# 433MHz_LNA.net
KiCad netlist of a schematic drawn in Altium Designer
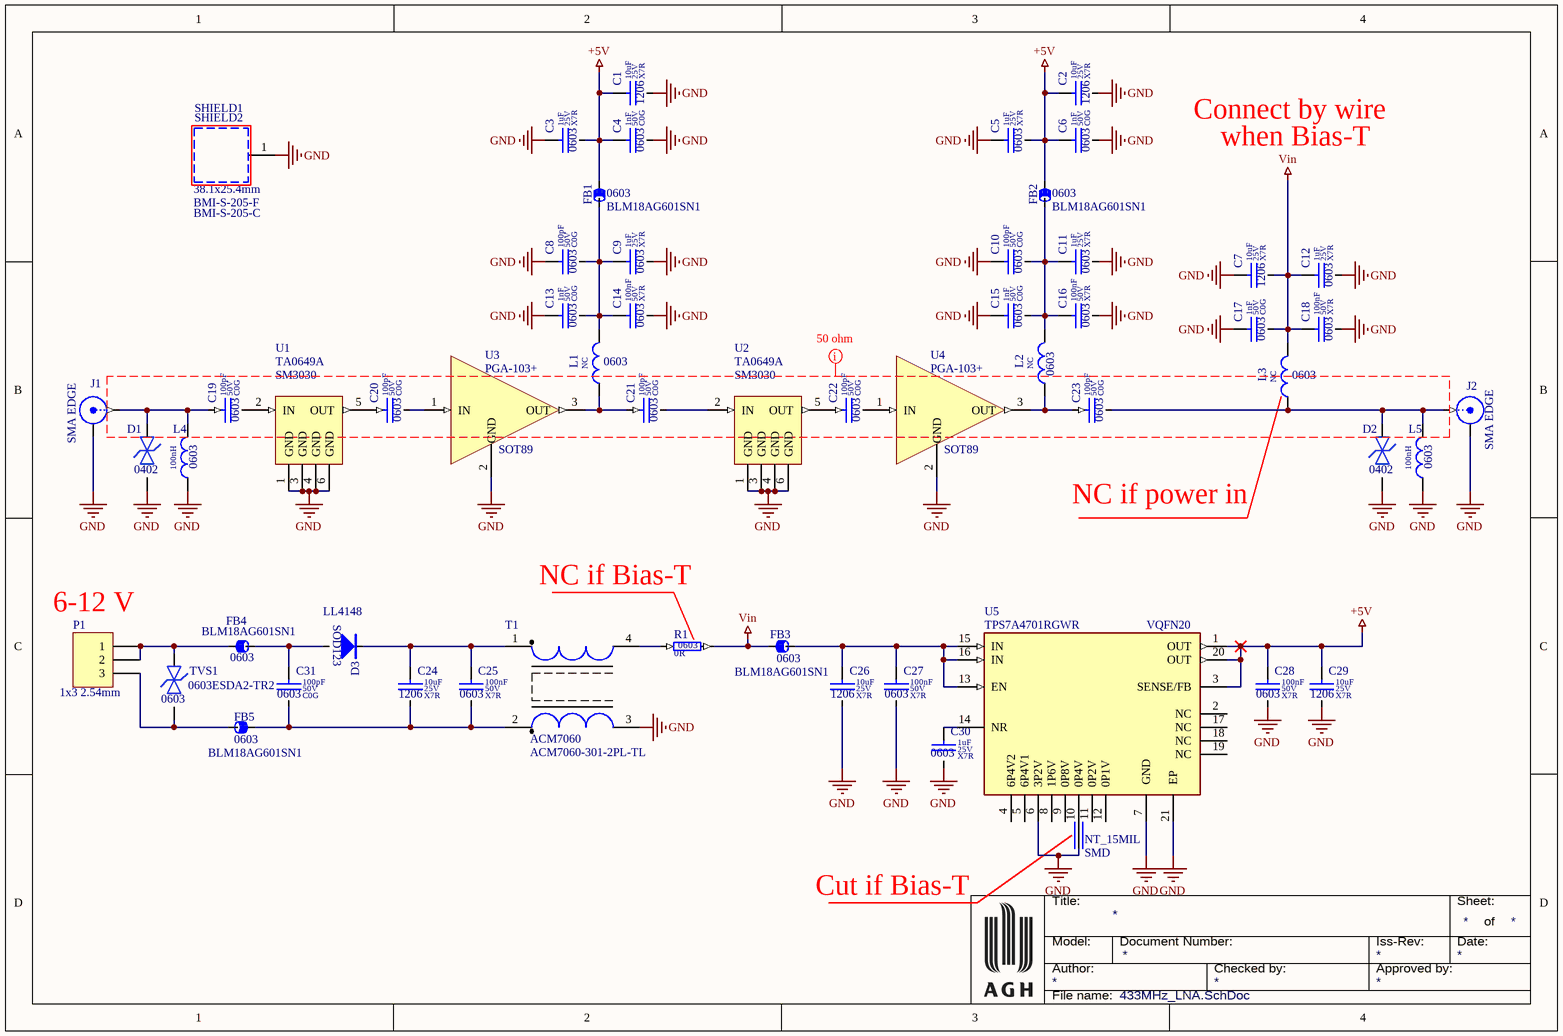
[diagram p0: 433MHz_LNA.SchDoc]

(export (version "E")
  (design (tool "Eeschema 10.0.6"))
  (components
    (comp (ref "C1")
      (value "10uF")
      (footprint "C_1206_3216")
      (description "Capacitor")
      (fields
        (field (name "DIELECTRIC") "X7R")
        (field (name "VOLTAGE") "25V")
        (field (name "SCH_FOOTPRINT") "1206")
        (field (name "PART NUMBER") "C_10uF_25V_X7R_1206_10")
        (field (name "MANUFACTURER") "Samsung Electro-Mechanics")
      )
      (libsource (lib "Library") (part "C"))
    )
    (comp (ref "C2")
      (value "10uF")
      (footprint "C_1206_3216")
      (description "Capacitor")
      (fields
        (field (name "DIELECTRIC") "X7R")
        (field (name "VOLTAGE") "25V")
        (field (name "SCH_FOOTPRINT") "1206")
        (field (name "PART NUMBER") "C_10uF_25V_X7R_1206_10")
        (field (name "MANUFACTURER") "Samsung Electro-Mechanics")
      )
      (libsource (lib "Library") (part "C"))
    )
    (comp (ref "C3")
      (value "1uF")
      (footprint "C_0603_1608")
      (description "Capacitor")
      (fields
        (field (name "DIELECTRIC") "X7R")
        (field (name "VOLTAGE") "25V")
        (field (name "SCH_FOOTPRINT") "0603")
        (field (name "PART NUMBER") "C_1uF_25V_X7R_0603_10")
        (field (name "MANUFACTURER") "Samsung")
      )
      (libsource (lib "Library") (part "C"))
    )
    (comp (ref "C4")
      (value "1nF")
      (footprint "C_0603_1608")
      (description "Capacitor")
      (fields
        (field (name "DIELECTRIC") "C0G")
        (field (name "VOLTAGE") "50V")
        (field (name "SCH_FOOTPRINT") "0603")
        (field (name "PART NUMBER") "C_1nF_50V_C0G_0603_5")
        (field (name "MANUFACTURER") "Samsung")
      )
      (libsource (lib "Library") (part "C"))
    )
    (comp (ref "C5")
      (value "1uF")
      (footprint "C_0603_1608")
      (description "Capacitor")
      (fields
        (field (name "DIELECTRIC") "X7R")
        (field (name "VOLTAGE") "25V")
        (field (name "SCH_FOOTPRINT") "0603")
        (field (name "PART NUMBER") "C_1uF_25V_X7R_0603_10")
        (field (name "MANUFACTURER") "Samsung")
      )
      (libsource (lib "Library") (part "C"))
    )
    (comp (ref "C6")
      (value "1nF")
      (footprint "C_0603_1608")
      (description "Capacitor")
      (fields
        (field (name "DIELECTRIC") "C0G")
        (field (name "VOLTAGE") "50V")
        (field (name "SCH_FOOTPRINT") "0603")
        (field (name "PART NUMBER") "C_1nF_50V_C0G_0603_5")
        (field (name "MANUFACTURER") "Samsung")
      )
      (libsource (lib "Library") (part "C"))
    )
    (comp (ref "C7")
      (value "10uF")
      (footprint "C_1206_3216")
      (description "Capacitor")
      (fields
        (field (name "DIELECTRIC") "X7R")
        (field (name "VOLTAGE") "25V")
        (field (name "SCH_FOOTPRINT") "1206")
        (field (name "PART NUMBER") "C_10uF_25V_X7R_1206_10")
        (field (name "MANUFACTURER") "Samsung Electro-Mechanics")
      )
      (libsource (lib "Library") (part "C"))
    )
    (comp (ref "C8")
      (value "100pF")
      (footprint "C_0603_1608")
      (description "Capacitor")
      (fields
        (field (name "DIELECTRIC") "C0G")
        (field (name "VOLTAGE") "50V")
        (field (name "SCH_FOOTPRINT") "0603")
        (field (name "PART NUMBER") "C_100pF_50V_C0G_0603_5")
        (field (name "MANUFACTURER") "AVX")
      )
      (libsource (lib "Library") (part "C"))
    )
    (comp (ref "C9")
      (value "1uF")
      (footprint "C_0603_1608")
      (description "Capacitor")
      (fields
        (field (name "DIELECTRIC") "X7R")
        (field (name "VOLTAGE") "25V")
        (field (name "SCH_FOOTPRINT") "0603")
        (field (name "PART NUMBER") "C_1uF_25V_X7R_0603_10")
        (field (name "MANUFACTURER") "Samsung")
      )
      (libsource (lib "Library") (part "C"))
    )
    (comp (ref "C10")
      (value "100pF")
      (footprint "C_0603_1608")
      (description "Capacitor")
      (fields
        (field (name "DIELECTRIC") "C0G")
        (field (name "VOLTAGE") "50V")
        (field (name "SCH_FOOTPRINT") "0603")
        (field (name "PART NUMBER") "C_100pF_50V_C0G_0603_5")
        (field (name "MANUFACTURER") "AVX")
      )
      (libsource (lib "Library") (part "C"))
    )
    (comp (ref "C11")
      (value "1uF")
      (footprint "C_0603_1608")
      (description "Capacitor")
      (fields
        (field (name "DIELECTRIC") "X7R")
        (field (name "VOLTAGE") "25V")
        (field (name "SCH_FOOTPRINT") "0603")
        (field (name "PART NUMBER") "C_1uF_25V_X7R_0603_10")
        (field (name "MANUFACTURER") "Samsung")
      )
      (libsource (lib "Library") (part "C"))
    )
    (comp (ref "C12")
      (value "1uF")
      (footprint "C_0603_1608")
      (description "Capacitor")
      (fields
        (field (name "DIELECTRIC") "X7R")
        (field (name "VOLTAGE") "25V")
        (field (name "SCH_FOOTPRINT") "0603")
        (field (name "PART NUMBER") "C_1uF_25V_X7R_0603_10")
        (field (name "MANUFACTURER") "Samsung")
      )
      (libsource (lib "Library") (part "C"))
    )
    (comp (ref "C13")
      (value "1nF")
      (footprint "C_0603_1608")
      (description "Capacitor")
      (fields
        (field (name "DIELECTRIC") "C0G")
        (field (name "VOLTAGE") "50V")
        (field (name "SCH_FOOTPRINT") "0603")
        (field (name "PART NUMBER") "C_1nF_50V_C0G_0603_5")
        (field (name "MANUFACTURER") "Samsung")
      )
      (libsource (lib "Library") (part "C"))
    )
    (comp (ref "C14")
      (value "100nF")
      (footprint "C_0603_1608")
      (description "Capacitor")
      (fields
        (field (name "DIELECTRIC") "X7R")
        (field (name "VOLTAGE") "50V")
        (field (name "SCH_FOOTPRINT") "0603")
        (field (name "PART NUMBER") "C_100nF_50V_X7R_0603_5")
        (field (name "MANUFACTURER") "Samsung")
      )
      (libsource (lib "Library") (part "C"))
    )
    (comp (ref "C15")
      (value "1nF")
      (footprint "C_0603_1608")
      (description "Capacitor")
      (fields
        (field (name "DIELECTRIC") "C0G")
        (field (name "VOLTAGE") "50V")
        (field (name "SCH_FOOTPRINT") "0603")
        (field (name "PART NUMBER") "C_1nF_50V_C0G_0603_5")
        (field (name "MANUFACTURER") "Samsung")
      )
      (libsource (lib "Library") (part "C"))
    )
    (comp (ref "C16")
      (value "100nF")
      (footprint "C_0603_1608")
      (description "Capacitor")
      (fields
        (field (name "DIELECTRIC") "X7R")
        (field (name "VOLTAGE") "50V")
        (field (name "SCH_FOOTPRINT") "0603")
        (field (name "PART NUMBER") "C_100nF_50V_X7R_0603_5")
        (field (name "MANUFACTURER") "Samsung")
      )
      (libsource (lib "Library") (part "C"))
    )
    (comp (ref "C17")
      (value "1nF")
      (footprint "C_0603_1608")
      (description "Capacitor")
      (fields
        (field (name "DIELECTRIC") "C0G")
        (field (name "VOLTAGE") "50V")
        (field (name "SCH_FOOTPRINT") "0603")
        (field (name "PART NUMBER") "C_1nF_50V_C0G_0603_5")
        (field (name "MANUFACTURER") "Samsung")
      )
      (libsource (lib "Library") (part "C"))
    )
    (comp (ref "C18")
      (value "100nF")
      (footprint "C_0603_1608")
      (description "Capacitor")
      (fields
        (field (name "DIELECTRIC") "X7R")
        (field (name "VOLTAGE") "50V")
        (field (name "SCH_FOOTPRINT") "0603")
        (field (name "PART NUMBER") "C_100nF_50V_X7R_0603_5")
        (field (name "MANUFACTURER") "Samsung")
      )
      (libsource (lib "Library") (part "C"))
    )
    (comp (ref "C19")
      (value "100pF")
      (footprint "C_0603_1608")
      (description "Capacitor")
      (fields
        (field (name "DIELECTRIC") "C0G")
        (field (name "VOLTAGE") "50V")
        (field (name "SCH_FOOTPRINT") "0603")
        (field (name "PART NUMBER") "C_100pF_50V_C0G_0603_5")
        (field (name "MANUFACTURER") "AVX")
      )
      (libsource (lib "") (part "C_1"))
    )
    (comp (ref "C20")
      (value "100pF")
      (footprint "C_0603_1608")
      (description "Capacitor")
      (fields
        (field (name "DIELECTRIC") "C0G")
        (field (name "VOLTAGE") "50V")
        (field (name "SCH_FOOTPRINT") "0603")
        (field (name "PART NUMBER") "C_100pF_50V_C0G_0603_5")
        (field (name "MANUFACTURER") "AVX")
      )
      (libsource (lib "") (part "C_1"))
    )
    (comp (ref "C21")
      (value "100pF")
      (footprint "C_0603_1608")
      (description "Capacitor")
      (fields
        (field (name "DIELECTRIC") "C0G")
        (field (name "VOLTAGE") "50V")
        (field (name "SCH_FOOTPRINT") "0603")
        (field (name "PART NUMBER") "C_100pF_50V_C0G_0603_5")
        (field (name "MANUFACTURER") "AVX")
      )
      (libsource (lib "") (part "C_1"))
    )
    (comp (ref "C22")
      (value "100pF")
      (footprint "C_0603_1608")
      (description "Capacitor")
      (fields
        (field (name "DIELECTRIC") "C0G")
        (field (name "VOLTAGE") "50V")
        (field (name "SCH_FOOTPRINT") "0603")
        (field (name "PART NUMBER") "C_100pF_50V_C0G_0603_5")
        (field (name "MANUFACTURER") "AVX")
      )
      (libsource (lib "") (part "C_1"))
    )
    (comp (ref "C23")
      (value "100pF")
      (footprint "C_0603_1608")
      (description "Capacitor")
      (fields
        (field (name "DIELECTRIC") "C0G")
        (field (name "VOLTAGE") "50V")
        (field (name "SCH_FOOTPRINT") "0603")
        (field (name "PART NUMBER") "C_100pF_50V_C0G_0603_5")
        (field (name "MANUFACTURER") "AVX")
      )
      (libsource (lib "") (part "C_1"))
    )
    (comp (ref "C24")
      (value "10uF")
      (footprint "C_1206_3216")
      (description "Capacitor")
      (fields
        (field (name "DIELECTRIC") "X7R")
        (field (name "VOLTAGE") "25V")
        (field (name "SCH_FOOTPRINT") "1206")
        (field (name "PART NUMBER") "C_10uF_25V_X7R_1206_10")
        (field (name "MANUFACTURER") "Samsung Electro-Mechanics")
      )
      (libsource (lib "Library") (part "C"))
    )
    (comp (ref "C25")
      (value "100nF")
      (footprint "C_0603_1608")
      (description "Capacitor")
      (fields
        (field (name "DIELECTRIC") "X7R")
        (field (name "VOLTAGE") "50V")
        (field (name "SCH_FOOTPRINT") "0603")
        (field (name "PART NUMBER") "C_100nF_50V_X7R_0603_5")
        (field (name "MANUFACTURER") "Samsung")
      )
      (libsource (lib "Library") (part "C"))
    )
    (comp (ref "C26")
      (value "10uF")
      (footprint "C_1206_3216")
      (description "Capacitor")
      (fields
        (field (name "DIELECTRIC") "X7R")
        (field (name "VOLTAGE") "25V")
        (field (name "SCH_FOOTPRINT") "1206")
        (field (name "PART NUMBER") "C_10uF_25V_X7R_1206_10")
        (field (name "MANUFACTURER") "Samsung Electro-Mechanics")
      )
      (libsource (lib "Library") (part "C"))
    )
    (comp (ref "C27")
      (value "100nF")
      (footprint "C_0603_1608")
      (description "Capacitor")
      (fields
        (field (name "DIELECTRIC") "X7R")
        (field (name "VOLTAGE") "50V")
        (field (name "SCH_FOOTPRINT") "0603")
        (field (name "PART NUMBER") "C_100nF_50V_X7R_0603_5")
        (field (name "MANUFACTURER") "Samsung")
      )
      (libsource (lib "Library") (part "C"))
    )
    (comp (ref "C28")
      (value "100nF")
      (footprint "C_0603_1608")
      (description "Capacitor")
      (fields
        (field (name "DIELECTRIC") "X7R")
        (field (name "VOLTAGE") "50V")
        (field (name "SCH_FOOTPRINT") "0603")
        (field (name "PART NUMBER") "C_100nF_50V_X7R_0603_5")
        (field (name "MANUFACTURER") "Samsung")
      )
      (libsource (lib "Library") (part "C"))
    )
    (comp (ref "C29")
      (value "10uF")
      (footprint "C_1206_3216")
      (description "Capacitor")
      (fields
        (field (name "DIELECTRIC") "X7R")
        (field (name "VOLTAGE") "25V")
        (field (name "SCH_FOOTPRINT") "1206")
        (field (name "PART NUMBER") "C_10uF_25V_X7R_1206_10")
        (field (name "MANUFACTURER") "Samsung Electro-Mechanics")
      )
      (libsource (lib "Library") (part "C"))
    )
    (comp (ref "C30")
      (value "1uF")
      (footprint "C_0603_1608")
      (description "Capacitor")
      (fields
        (field (name "DIELECTRIC") "X7R")
        (field (name "VOLTAGE") "25V")
        (field (name "SCH_FOOTPRINT") "0603")
        (field (name "PART NUMBER") "C_1uF_25V_X7R_0603_10")
        (field (name "MANUFACTURER") "Samsung")
      )
      (libsource (lib "Library") (part "C"))
    )
    (comp (ref "C31")
      (value "100pF")
      (footprint "C_0603_1608")
      (description "Capacitor")
      (fields
        (field (name "DIELECTRIC") "C0G")
        (field (name "VOLTAGE") "50V")
        (field (name "SCH_FOOTPRINT") "0603")
        (field (name "PART NUMBER") "C_100pF_50V_C0G_0603_5")
        (field (name "MANUFACTURER") "AVX")
      )
      (libsource (lib "Library") (part "C"))
    )
    (comp (ref "D1")
      (value "ESD Suppressors / TVS Diodes")
      (footprint "D_BI_0402_1005")
      (fields
        (field (name "SCH_FOOTPRINT") "0402")
        (field (name "PART NUMBER") "TVS_PS04LTVA1")
        (field (name "VOLTAGE") "12V")
        (field (name "MANUFACTURER") "Bussmann")
      )
      (libsource (lib "Library") (part "TVS_BI"))
    )
    (comp (ref "D2")
      (value "ESD Suppressors / TVS Diodes")
      (footprint "D_BI_0402_1005")
      (fields
        (field (name "SCH_FOOTPRINT") "0402")
        (field (name "PART NUMBER") "TVS_PS04LTVA1")
        (field (name "VOLTAGE") "12V")
        (field (name "MANUFACTURER") "Bussmann")
      )
      (libsource (lib "Library") (part "TVS_BI"))
    )
    (comp (ref "D3")
      (value "LL4148")
      (footprint "SOD123")
      (fields
        (field (name "PART NUMBER") "D_1N4148W_0A15_75V_SOD123")
        (field (name "VOLTAGE") "75V")
        (field (name "MANUFACTURER") "Fairchild Semiconductor")
      )
      (libsource (lib "Library") (part "D"))
    )
    (comp (ref "FB1")
      (value "BLM18AG601SN1")
      (footprint "FB_0603_1608")
      (description "Ferrite Bead")
      (fields
        (field (name "PART NUMBER") "FB_BLM18AG601SN1")
        (field (name "SCH_FOOTPRINT") "0603")
        (field (name "MANUFACTURER") "Murata")
      )
      (libsource (lib "Library") (part "FB"))
    )
    (comp (ref "FB2")
      (value "BLM18AG601SN1")
      (footprint "FB_0603_1608")
      (description "Ferrite Bead")
      (fields
        (field (name "PART NUMBER") "FB_BLM18AG601SN1")
        (field (name "SCH_FOOTPRINT") "0603")
        (field (name "MANUFACTURER") "Murata")
      )
      (libsource (lib "Library") (part "FB"))
    )
    (comp (ref "FB3")
      (value "BLM18AG601SN1")
      (footprint "FB_0603_1608")
      (description "Ferrite Bead")
      (fields
        (field (name "PART NUMBER") "FB_BLM18AG601SN1")
        (field (name "SCH_FOOTPRINT") "0603")
        (field (name "MANUFACTURER") "Murata")
      )
      (libsource (lib "") (part "FB_2"))
    )
    (comp (ref "FB4")
      (value "BLM18AG601SN1")
      (footprint "FB_0603_1608")
      (description "Ferrite Bead")
      (fields
        (field (name "PART NUMBER") "FB_BLM18AG601SN1")
        (field (name "SCH_FOOTPRINT") "0603")
        (field (name "MANUFACTURER") "Murata")
      )
      (libsource (lib "") (part "FB_2"))
    )
    (comp (ref "FB5")
      (value "BLM18AG601SN1")
      (footprint "FB_0603_1608")
      (description "Ferrite Bead")
      (fields
        (field (name "PART NUMBER") "FB_BLM18AG601SN1")
        (field (name "SCH_FOOTPRINT") "0603")
        (field (name "MANUFACTURER") "Murata")
      )
      (libsource (lib "") (part "FB_1"))
    )
    (comp (ref "J1")
      (value "SMA EDGE")
      (footprint "J_SMA_EDGE_6.25")
      (description "SMA connector")
      (fields
        (field (name "PART NUMBER") "J_SMA_EDGE_6.25")
        (field (name "SCH_FOOTPRINT") "SMA EDGE")
        (field (name "MANUFACTURER") "Adam Tech")
      )
      (libsource (lib "Library") (part "J_SMA"))
    )
    (comp (ref "J2")
      (value "SMA EDGE")
      (footprint "J_SMA_EDGE_6.25")
      (description "SMA connector")
      (fields
        (field (name "PART NUMBER") "J_SMA_EDGE_6.25")
        (field (name "SCH_FOOTPRINT") "SMA EDGE")
        (field (name "MANUFACTURER") "Adam Tech")
      )
      (libsource (lib "") (part "J_SMA_1"))
    )
    (comp (ref "L1")
      (value "NC")
      (footprint "L_0603_1608")
      (description "Induction")
      (fields
        (field (name "SCH_FOOTPRINT") "0603")
        (field (name "PART NUMBER") "L_0603")
        (field (name "Comment") "L")
      )
      (libsource (lib "Library") (part "L"))
    )
    (comp (ref "L2")
      (value "NC")
      (footprint "L_0603_1608")
      (description "Induction")
      (fields
        (field (name "SCH_FOOTPRINT") "0603")
        (field (name "PART NUMBER") "L_0603")
        (field (name "Comment") "L")
      )
      (libsource (lib "Library") (part "L"))
    )
    (comp (ref "L3")
      (value "NC")
      (footprint "L_0603_1608")
      (description "Induction")
      (fields
        (field (name "SCH_FOOTPRINT") "0603")
        (field (name "PART NUMBER") "L_0603")
        (field (name "Comment") "L")
      )
      (libsource (lib "Library") (part "L"))
    )
    (comp (ref "L4")
      (value "100nH")
      (footprint "L_0603_1608")
      (description "Induction")
      (fields
        (field (name "SCH_FOOTPRINT") "0603")
        (field (name "PART NUMBER") "L_100NH_0A3_0603")
        (field (name "MANUFACTURER") "Bourns")
      )
      (libsource (lib "Library") (part "L"))
    )
    (comp (ref "L5")
      (value "100nH")
      (footprint "L_0603_1608")
      (description "Induction")
      (fields
        (field (name "SCH_FOOTPRINT") "0603")
        (field (name "PART NUMBER") "L_100NH_0A3_0603")
        (field (name "MANUFACTURER") "Bourns")
      )
      (libsource (lib "Library") (part "L"))
    )
    (comp (ref "NT1")
      (value "NT_15MIL")
      (footprint "NT_15MIL")
      (fields (field (name "SCH_FOOTPRINT") "SMD") (field (name "Comment") "NETTIE 15MIL"))
      (libsource (lib "Library") (part "NET_TIE"))
    )
    (comp (ref "P1")
      (value "Goldpin")
      (footprint "P_HEADER_1x3_2.54")
      (description "Header, 3-Pin")
      (fields
        (field (name "PART NUMBER") "P_HEADER_1x3_2.54")
        (field (name "SCH_FOOTPRINT") "1x3 2.54mm")
        (field (name "MANUFACTURER") "Connfly")
      )
      (libsource (lib "Library") (part "P_HEADER_1x3"))
    )
    (comp (ref "R1")
      (value "0R")
      (footprint "R_0603_1608")
      (fields
        (field (name "SCH_FOOTPRINT") "0603")
        (field (name "PART NUMBER") "R_0R_0603")
        (field (name "MANUFACTURER PART NUMBER") "RC1608J000CS")
        (field (name "Comment") "Resistor")
      )
      (libsource (lib "Library") (part "R"))
    )
    (comp (ref "SHIELD1")
      (value "BMI-S-205-C")
      (footprint "BMI-S-205-C")
      (description "Shield, 1 pad")
      (fields (field (name "PART NUMBER") "SHIELD_BMI-S-205-C") (field (name "MANUFACTURER") "Laird"))
      (libsource (lib "Library") (part "SHIELD_COVER"))
    )
    (comp (ref "SHIELD2")
      (value "BMI-S-205-F")
      (footprint "BMI-S-205-F")
      (description "Shield, 1 pad")
      (fields
        (field (name "PART NUMBER") "SHIELD_BMI-S-205-F")
        (field (name "SCH_FOOTPRINT") "38.1x25.4mm")
        (field (name "MANUFACTURER") "Laird")
      )
      (libsource (lib "Library") (part "SHIELD"))
    )
    (comp (ref "T1")
      (value "ACM7060-301-2PL-TL")
      (footprint "ACM7060")
      (description "TDK ACM7060 common mode filter")
      (fields
        (field (name "SCH_FOOTPRINT") "ACM7060")
        (field (name "VOLTAGE") "80")
        (field (name "MANUFACTURER") "TDK")
      )
      (libsource (lib "Library") (part "LM_ACM7060"))
    )
    (comp (ref "TVS1")
      (value "0603ESDA2-TR2")
      (footprint "R_0603_1608")
      (fields
        (field (name "SCH_FOOTPRINT") "0603")
        (field (name "PART NUMBER") "TVS_0603ESDA2")
        (field (name "VOLTAGE") "14V")
        (field (name "MANUFACTURER") "Bussmann")
      )
      (libsource (lib "Library") (part "TVS_BI"))
    )
    (comp (ref "U1")
      (value "TA0649A")
      (footprint "SAW_DCC6_SM3030-6_3x3")
      (fields
        (field (name "PART NUMBER") "U_TA0649A")
        (field (name "SCH_FOOTPRINT") "SM3030")
        (field (name "MANUFACTURER") "Tai-Saw")
      )
      (libsource (lib "Library") (part "U_SAW6_2_5"))
    )
    (comp (ref "U2")
      (value "TA0649A")
      (footprint "SAW_DCC6_SM3030-6_3x3")
      (fields
        (field (name "PART NUMBER") "U_TA0649A")
        (field (name "SCH_FOOTPRINT") "SM3030")
        (field (name "MANUFACTURER") "Tai-Saw")
      )
      (libsource (lib "Library") (part "U_SAW6_2_5"))
    )
    (comp (ref "U3")
      (value "PGA-103+")
      (footprint "SOT89_TO-243AA_N")
      (fields
        (field (name "PART NUMBER") "U_PGA103+")
        (field (name "SCH_FOOTPRINT") "SOT89")
        (field (name "MANUFACTURER") "Mini-Circuits")
        (field (name "Comment") "PGA103+")
      )
      (libsource (lib "Library") (part "U_PGA103+"))
    )
    (comp (ref "U4")
      (value "PGA-103+")
      (footprint "SOT89_TO-243AA_N")
      (fields
        (field (name "PART NUMBER") "U_PGA103+")
        (field (name "SCH_FOOTPRINT") "SOT89")
        (field (name "MANUFACTURER") "Mini-Circuits")
        (field (name "Comment") "PGA103+")
      )
      (libsource (lib "Library") (part "U_PGA103+"))
    )
    (comp (ref "U5")
      (value "TPS7A4701RGWR")
      (footprint "QFN20_5x5")
      (description "RF LDO Voltage Regulator")
      (fields
        (field (name "SCH_FOOTPRINT") "VQFN20")
        (field (name "PART NUMBER") "VL_TPS7A4701RGWR_ADJ_1A")
        (field (name "VOLTAGE") "ADJ")
      )
      (libsource (lib "Library") (part "VL_TPS7A470X"))
    )
  )
  (nets
    (net (code "1") (name "+5V") (class "Default")
      (node (ref "C1") (pin "1") (pinfunction "1_1") (pintype "passive"))
      (node (ref "C2") (pin "1") (pinfunction "1_1") (pintype "passive"))
      (node (ref "C28") (pin "1") (pinfunction "1_1") (pintype "passive"))
      (node (ref "C29") (pin "1") (pinfunction "1_1") (pintype "passive"))
      (node (ref "C3") (pin "2") (pinfunction "2_2") (pintype "passive"))
      (node (ref "C4") (pin "1") (pinfunction "1_1") (pintype "passive"))
      (node (ref "C5") (pin "2") (pinfunction "2_2") (pintype "passive"))
      (node (ref "C6") (pin "1") (pinfunction "1_1") (pintype "passive"))
      (node (ref "FB1") (pin "1") (pintype "input"))
      (node (ref "FB2") (pin "1") (pintype "input"))
      (node (ref "U5") (pin "1") (pinfunction "OUT_1") (pintype "output"))
      (node (ref "U5") (pin "20") (pinfunction "OUT_20") (pintype "output"))
      (node (ref "U5") (pin "3") (pinfunction "SENSE/FB_3") (pintype "passive"))
    )
    (net (code "2") (name "GND") (class "Default")
      (node (ref "C1") (pin "2") (pinfunction "2_2") (pintype "passive"))
      (node (ref "C10") (pin "1") (pinfunction "1_1") (pintype "passive"))
      (node (ref "C11") (pin "2") (pinfunction "2_2") (pintype "passive"))
      (node (ref "C12") (pin "2") (pinfunction "2_2") (pintype "passive"))
      (node (ref "C13") (pin "1") (pinfunction "1_1") (pintype "passive"))
      (node (ref "C14") (pin "2") (pinfunction "2_2") (pintype "passive"))
      (node (ref "C15") (pin "1") (pinfunction "1_1") (pintype "passive"))
      (node (ref "C16") (pin "2") (pinfunction "2_2") (pintype "passive"))
      (node (ref "C17") (pin "1") (pinfunction "1_1") (pintype "passive"))
      (node (ref "C18") (pin "2") (pinfunction "2_2") (pintype "passive"))
      (node (ref "C2") (pin "2") (pinfunction "2_2") (pintype "passive"))
      (node (ref "C26") (pin "2") (pinfunction "2_2") (pintype "passive"))
      (node (ref "C27") (pin "2") (pinfunction "2_2") (pintype "passive"))
      (node (ref "C28") (pin "2") (pinfunction "2_2") (pintype "passive"))
      (node (ref "C29") (pin "2") (pinfunction "2_2") (pintype "passive"))
      (node (ref "C3") (pin "1") (pinfunction "1_1") (pintype "passive"))
      (node (ref "C30") (pin "2") (pinfunction "2_2") (pintype "passive"))
      (node (ref "C4") (pin "2") (pinfunction "2_2") (pintype "passive"))
      (node (ref "C5") (pin "1") (pinfunction "1_1") (pintype "passive"))
      (node (ref "C6") (pin "2") (pinfunction "2_2") (pintype "passive"))
      (node (ref "C7") (pin "1") (pinfunction "1_1") (pintype "passive"))
      (node (ref "C8") (pin "1") (pinfunction "1_1") (pintype "passive"))
      (node (ref "C9") (pin "2") (pinfunction "2_2") (pintype "passive"))
      (node (ref "D1") (pin "2") (pinfunction "2_2") (pintype "passive"))
      (node (ref "D2") (pin "2") (pinfunction "2_2") (pintype "passive"))
      (node (ref "J1") (pin "2") (pinfunction "Y_2") (pintype "passive"))
      (node (ref "J2") (pin "2") (pinfunction "Y_2") (pintype "passive"))
      (node (ref "L4") (pin "1") (pinfunction "1_1") (pintype "passive"))
      (node (ref "L5") (pin "1") (pinfunction "1_1") (pintype "passive"))
      (node (ref "NT1") (pin "1") (pinfunction "1_1") (pintype "passive"))
      (node (ref "SHIELD2") (pin "1") (pinfunction "shield_1") (pintype "passive"))
      (node (ref "T1") (pin "3") (pinfunction "3_3") (pintype "passive"))
      (node (ref "U1") (pin "1") (pinfunction "GND_1") (pintype "power_in"))
      (node (ref "U1") (pin "3") (pinfunction "GND_3") (pintype "power_in"))
      (node (ref "U1") (pin "4") (pinfunction "GND_4") (pintype "power_in"))
      (node (ref "U1") (pin "6") (pinfunction "GND_6") (pintype "power_in"))
      (node (ref "U2") (pin "1") (pinfunction "GND_1") (pintype "power_in"))
      (node (ref "U2") (pin "3") (pinfunction "GND_3") (pintype "power_in"))
      (node (ref "U2") (pin "4") (pinfunction "GND_4") (pintype "power_in"))
      (node (ref "U2") (pin "6") (pinfunction "GND_6") (pintype "power_in"))
      (node (ref "U3") (pin "2") (pinfunction "GND_2") (pintype "power_in"))
      (node (ref "U4") (pin "2") (pinfunction "GND_2") (pintype "power_in"))
      (node (ref "U5") (pin "21") (pinfunction "EP_21") (pintype "power_in"))
      (node (ref "U5") (pin "6") (pinfunction "3P2V_6") (pintype "passive"))
      (node (ref "U5") (pin "7") (pinfunction "GND_7") (pintype "power_in"))
    )
    (net (code "3") (name "Net-(C10-Pad2)") (class "Default")
      (node (ref "C10") (pin "2") (pinfunction "2_2") (pintype "passive"))
      (node (ref "C11") (pin "1") (pinfunction "1_1") (pintype "passive"))
      (node (ref "C15") (pin "2") (pinfunction "2_2") (pintype "passive"))
      (node (ref "C16") (pin "1") (pinfunction "1_1") (pintype "passive"))
      (node (ref "FB2") (pin "2") (pintype "output"))
      (node (ref "L2") (pin "2") (pinfunction "2_2") (pintype "passive"))
    )
    (net (code "4") (name "Net-(C13-Pad2)") (class "Default")
      (node (ref "C13") (pin "2") (pinfunction "2_2") (pintype "passive"))
      (node (ref "C14") (pin "1") (pinfunction "1_1") (pintype "passive"))
      (node (ref "C8") (pin "2") (pinfunction "2_2") (pintype "passive"))
      (node (ref "C9") (pin "1") (pinfunction "1_1") (pintype "passive"))
      (node (ref "FB1") (pin "2") (pintype "output"))
      (node (ref "L1") (pin "2") (pinfunction "2_2") (pintype "passive"))
    )
    (net (code "5") (name "Net-(C24-Pad1)") (class "Default")
      (node (ref "C24") (pin "1") (pinfunction "1_1") (pintype "passive"))
      (node (ref "C25") (pin "1") (pinfunction "1_1") (pintype "passive"))
      (node (ref "D3") (pin "1") (pintype "passive"))
      (node (ref "T1") (pin "1") (pinfunction "1_1") (pintype "passive"))
    )
    (net (code "6") (name "Net-(C24-Pad2)") (class "Default")
      (node (ref "C24") (pin "2") (pinfunction "2_2") (pintype "passive"))
      (node (ref "C25") (pin "2") (pinfunction "2_2") (pintype "passive"))
      (node (ref "C31") (pin "2") (pinfunction "2_2") (pintype "passive"))
      (node (ref "FB5") (pin "1") (pintype "input"))
      (node (ref "T1") (pin "2") (pinfunction "2_2") (pintype "passive"))
    )
    (net (code "7") (name "Net-(C31-Pad1)") (class "Default")
      (node (ref "C31") (pin "1") (pinfunction "1_1") (pintype "passive"))
      (node (ref "D3") (pin "2") (pintype "passive"))
      (node (ref "FB4") (pin "2") (pintype "output"))
    )
    (net (code "8") (name "Net-(FB4-Pad1)") (class "Default")
      (node (ref "FB4") (pin "1") (pintype "input"))
      (node (ref "P1") (pin "1") (pinfunction "1_1") (pintype "passive"))
      (node (ref "P1") (pin "2") (pinfunction "2_2") (pintype "passive"))
      (node (ref "TVS1") (pin "1") (pinfunction "1_1") (pintype "passive"))
    )
    (net (code "9") (name "Net-(FB5-Pad2)") (class "Default")
      (node (ref "FB5") (pin "2") (pintype "output"))
      (node (ref "P1") (pin "3") (pinfunction "3_3") (pintype "passive"))
      (node (ref "TVS1") (pin "2") (pinfunction "2_2") (pintype "passive"))
    )
    (net (code "10") (name "Net-(J1-X)") (class "Default")
      (node (ref "C19") (pin "1") (pinfunction "1_1") (pintype "input"))
      (node (ref "D1") (pin "1") (pinfunction "1_1") (pintype "passive"))
      (node (ref "J1") (pin "1") (pinfunction "X_1") (pintype "output"))
      (node (ref "L4") (pin "2") (pinfunction "2_2") (pintype "passive"))
    )
    (net (code "11") (name "Net-(J2-X)") (class "Default")
      (node (ref "C23") (pin "2") (pinfunction "2_2") (pintype "output"))
      (node (ref "D2") (pin "1") (pinfunction "1_1") (pintype "passive"))
      (node (ref "J2") (pin "1") (pinfunction "X_1") (pintype "input"))
      (node (ref "L3") (pin "1") (pinfunction "1_1") (pintype "passive"))
      (node (ref "L5") (pin "2") (pinfunction "2_2") (pintype "passive"))
    )
    (net (code "12") (name "Net-(R1-Pad1)") (class "Default")
      (node (ref "R1") (pin "1") (pinfunction "1_1") (pintype "input"))
      (node (ref "T1") (pin "4") (pinfunction "4_4") (pintype "passive"))
    )
    (net (code "13") (name "Net-(U1-IN)") (class "Default")
      (node (ref "C19") (pin "2") (pinfunction "2_2") (pintype "output"))
      (node (ref "U1") (pin "2") (pinfunction "IN_2") (pintype "input"))
    )
    (net (code "14") (name "Net-(U1-OUT)") (class "Default")
      (node (ref "C20") (pin "1") (pinfunction "1_1") (pintype "input"))
      (node (ref "U1") (pin "5") (pinfunction "OUT_5") (pintype "output"))
    )
    (net (code "15") (name "Net-(U2-IN)") (class "Default")
      (node (ref "C21") (pin "2") (pinfunction "2_2") (pintype "output"))
      (node (ref "U2") (pin "2") (pinfunction "IN_2") (pintype "input"))
    )
    (net (code "16") (name "Net-(U2-OUT)") (class "Default")
      (node (ref "C22") (pin "1") (pinfunction "1_1") (pintype "input"))
      (node (ref "U2") (pin "5") (pinfunction "OUT_5") (pintype "output"))
    )
    (net (code "17") (name "Net-(U3-IN)") (class "Default")
      (node (ref "C20") (pin "2") (pinfunction "2_2") (pintype "output"))
      (node (ref "U3") (pin "1") (pinfunction "IN_1") (pintype "input"))
    )
    (net (code "18") (name "Net-(U3-OUT)") (class "Default")
      (node (ref "C21") (pin "1") (pinfunction "1_1") (pintype "input"))
      (node (ref "L1") (pin "1") (pinfunction "1_1") (pintype "passive"))
      (node (ref "U3") (pin "3") (pinfunction "OUT_3") (pintype "output"))
    )
    (net (code "19") (name "Net-(U4-IN)") (class "Default")
      (node (ref "C22") (pin "2") (pinfunction "2_2") (pintype "output"))
      (node (ref "U4") (pin "1") (pinfunction "IN_1") (pintype "input"))
    )
    (net (code "20") (name "Net-(U4-OUT)") (class "Default")
      (node (ref "C23") (pin "1") (pinfunction "1_1") (pintype "input"))
      (node (ref "L2") (pin "1") (pinfunction "1_1") (pintype "passive"))
      (node (ref "U4") (pin "3") (pinfunction "OUT_3") (pintype "output"))
    )
    (net (code "21") (name "Net-(U5-0P4V)") (class "Default")
      (node (ref "NT1") (pin "2") (pinfunction "2_2") (pintype "passive"))
      (node (ref "U5") (pin "10") (pinfunction "0P4V_10") (pintype "passive"))
    )
    (net (code "22") (name "Net-(U5-EN)") (class "Default")
      (node (ref "C26") (pin "1") (pinfunction "1_1") (pintype "passive"))
      (node (ref "C27") (pin "1") (pinfunction "1_1") (pintype "passive"))
      (node (ref "FB3") (pin "2") (pintype "output"))
      (node (ref "U5") (pin "13") (pinfunction "EN_13") (pintype "input"))
      (node (ref "U5") (pin "15") (pinfunction "IN_15") (pintype "input"))
      (node (ref "U5") (pin "16") (pinfunction "IN_16") (pintype "input"))
    )
    (net (code "23") (name "Net-(U5-NR)") (class "Default")
      (node (ref "C30") (pin "1") (pinfunction "1_1") (pintype "passive"))
      (node (ref "U5") (pin "14") (pinfunction "NR_14") (pintype "passive"))
    )
    (net (code "24") (name "Vin") (class "Default")
      (node (ref "C12") (pin "1") (pinfunction "1_1") (pintype "passive"))
      (node (ref "C17") (pin "2") (pinfunction "2_2") (pintype "passive"))
      (node (ref "C18") (pin "1") (pinfunction "1_1") (pintype "passive"))
      (node (ref "C7") (pin "2") (pinfunction "2_2") (pintype "passive"))
      (node (ref "FB3") (pin "1") (pintype "input"))
      (node (ref "L3") (pin "2") (pinfunction "2_2") (pintype "passive"))
      (node (ref "R1") (pin "2") (pinfunction "2_2") (pintype "output"))
    )
    (net (code "25") (name "unconnected-(U5-0P1V-Pad12)") (class "Default")
      (node (ref "U5") (pin "12") (pinfunction "0P1V_12") (pintype "passive"))
    )
    (net (code "26") (name "unconnected-(U5-0P2V-Pad11)") (class "Default")
      (node (ref "U5") (pin "11") (pinfunction "0P2V_11") (pintype "passive"))
    )
    (net (code "27") (name "unconnected-(U5-0P8V-Pad9)") (class "Default")
      (node (ref "U5") (pin "9") (pinfunction "0P8V_9") (pintype "passive"))
    )
    (net (code "28") (name "unconnected-(U5-1P6V-Pad8)") (class "Default")
      (node (ref "U5") (pin "8") (pinfunction "1P6V_8") (pintype "passive"))
    )
    (net (code "29") (name "unconnected-(U5-6P4V1-Pad5)") (class "Default")
      (node (ref "U5") (pin "5") (pinfunction "6P4V1_5") (pintype "passive"))
    )
    (net (code "30") (name "unconnected-(U5-6P4V2-Pad4)") (class "Default")
      (node (ref "U5") (pin "4") (pinfunction "6P4V2_4") (pintype "passive"))
    )
    (net (code "31") (name "unconnected-(U5-NC-Pad2)") (class "Default")
      (node (ref "U5") (pin "2") (pinfunction "NC_2") (pintype "passive"))
    )
    (net (code "32") (name "unconnected-(U5-NC-Pad17)") (class "Default")
      (node (ref "U5") (pin "17") (pinfunction "NC_17") (pintype "passive"))
    )
    (net (code "33") (name "unconnected-(U5-NC-Pad18)") (class "Default")
      (node (ref "U5") (pin "18") (pinfunction "NC_18") (pintype "passive"))
    )
    (net (code "34") (name "unconnected-(U5-NC-Pad19)") (class "Default")
      (node (ref "U5") (pin "19") (pinfunction "NC_19") (pintype "passive"))
    )
  )
)
